# PSU_MGTAVCC_Buck.net
KiCad netlist of a schematic drawn in Altium Designer
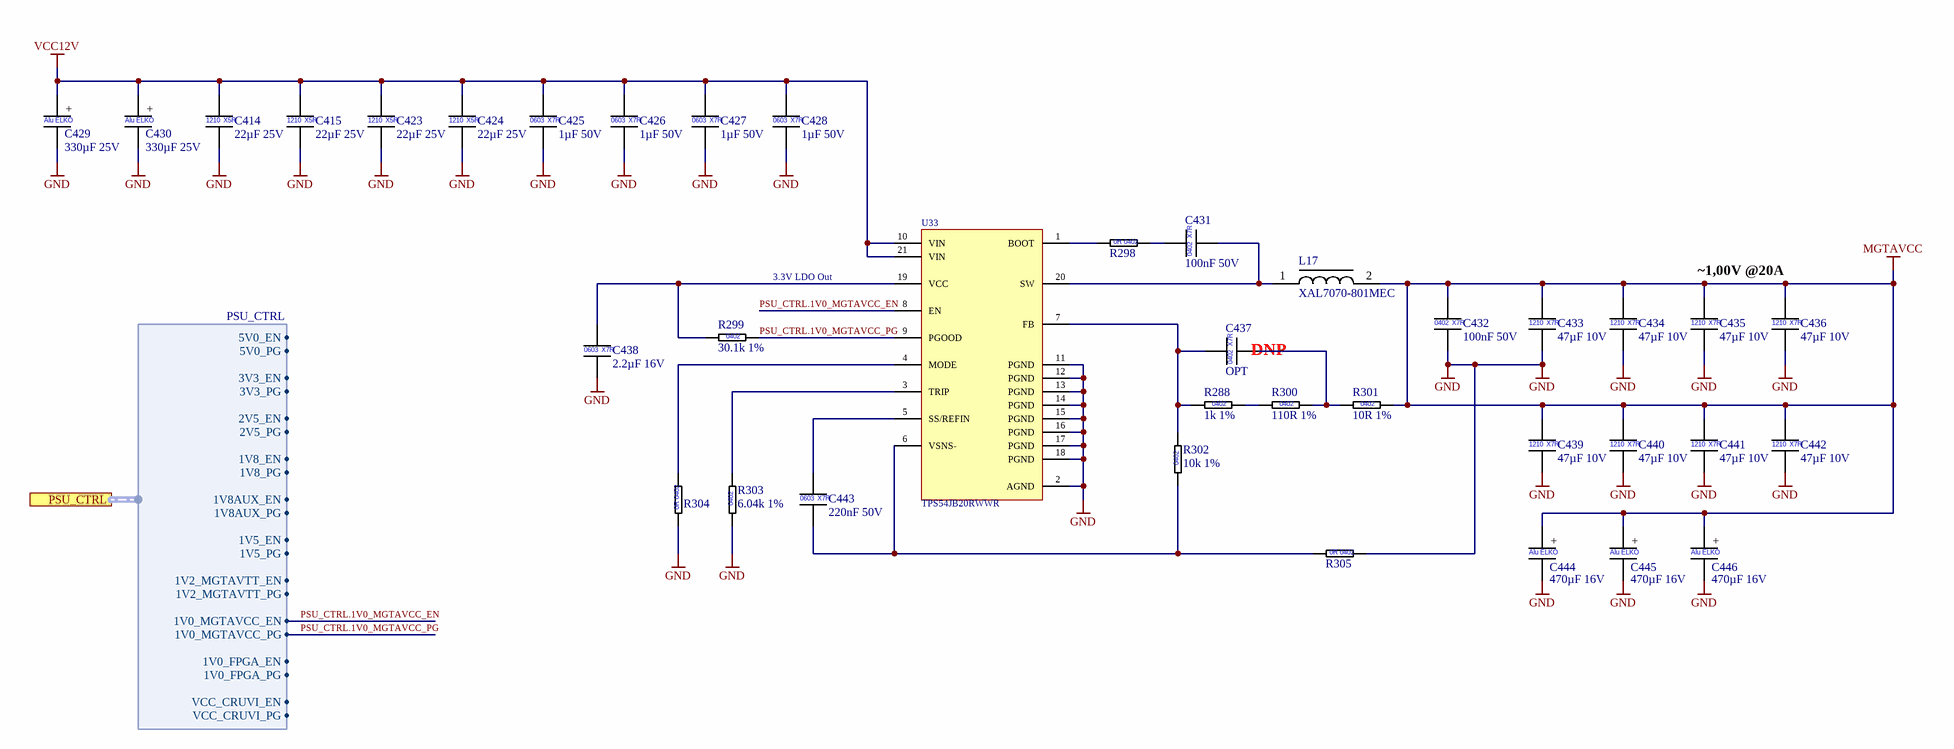
[diagram p0: PSU_MGTAVCC_Buck.SchDoc]

(export (version "E")
  (design (tool "Eeschema 10.0.6"))
  (components
    (comp (ref "C414")
      (value "22µF 25V")
      (footprint "Cap:CAP_1210")
      (description "Multilayer Ceramic Capacitors MLCC - SMD/SMT 1210 25VDC")
      (libsource (lib "Cap") (part "CAP_1210_22µF_25V"))
    )
    (comp (ref "C415")
      (value "22µF 25V")
      (footprint "Cap:CAP_1210")
      (description "Multilayer Ceramic Capacitors MLCC - SMD/SMT 1210 25VDC")
      (libsource (lib "Cap") (part "CAP_1210_22µF_25V"))
    )
    (comp (ref "C423")
      (value "22µF 25V")
      (footprint "Cap:CAP_1210")
      (description "Multilayer Ceramic Capacitors MLCC - SMD/SMT 1210 25VDC")
      (libsource (lib "Cap") (part "CAP_1210_22µF_25V"))
    )
    (comp (ref "C424")
      (value "22µF 25V")
      (footprint "Cap:CAP_1210")
      (description "Multilayer Ceramic Capacitors MLCC - SMD/SMT 1210 25VDC")
      (libsource (lib "Cap") (part "CAP_1210_22µF_25V"))
    )
    (comp (ref "C425")
      (value "1µF 50V")
      (footprint "CAP_0603")
      (description "Multilayer Ceramic Capacitors MLCC - SMD/SMT 50V 1uF X7R 0603 10%")
      (libsource (lib "Cap") (part "CAP_0603_1µF_50V_X7R_10%"))
    )
    (comp (ref "C426")
      (value "1µF 50V")
      (footprint "CAP_0603")
      (description "Multilayer Ceramic Capacitors MLCC - SMD/SMT 50V 1uF X7R 0603 10%")
      (libsource (lib "Cap") (part "CAP_0603_1µF_50V_X7R_10%"))
    )
    (comp (ref "C427")
      (value "1µF 50V")
      (footprint "CAP_0603")
      (description "Multilayer Ceramic Capacitors MLCC - SMD/SMT 50V 1uF X7R 0603 10%")
      (libsource (lib "Cap") (part "CAP_0603_1µF_50V_X7R_10%"))
    )
    (comp (ref "C428")
      (value "1µF 50V")
      (footprint "CAP_0603")
      (description "Multilayer Ceramic Capacitors MLCC - SMD/SMT 50V 1uF X7R 0603 10%")
      (libsource (lib "Cap") (part "CAP_0603_1µF_50V_X7R_10%"))
    )
    (comp (ref "C429")
      (value "330µF 25V")
      (footprint "Cap:WCAP-PTG5_D10H12.5")
      (description "Organische Polymer-Aluminiumkondensatoren 330uF 25 Volts 20% AEC-Q200")
      (libsource (lib "Cap") (part "CAP_D10L12.5_330µF_25V"))
    )
    (comp (ref "C430")
      (value "330µF 25V")
      (footprint "Cap:WCAP-PTG5_D10H12.5")
      (description "Organische Polymer-Aluminiumkondensatoren 330uF 25 Volts 20% AEC-Q200")
      (libsource (lib "Cap") (part "CAP_D10L12.5_330µF_25V"))
    )
    (comp (ref "C431")
      (value "100nF 50V")
      (footprint "Cap:CAP_0402")
      (description "Multilayer Ceramic Capacitors MLCC - SMD/SMT 0402 50VDC")
      (libsource (lib "Cap") (part "CAP_0402_100nF_50V"))
    )
    (comp (ref "C432")
      (value "100nF 50V")
      (footprint "Cap:CAP_0402")
      (description "Multilayer Ceramic Capacitors MLCC - SMD/SMT 0402 50VDC")
      (libsource (lib "") (part "CAP_0402_100nF_50V_1"))
    )
    (comp (ref "C433")
      (value "47µF 10V")
      (footprint "Cap:CAP_1210")
      (description "Multilayer Ceramic Capacitors MLCC - SMD/SMT 47 uF 10 VDC 10% 1210 X7R")
      (libsource (lib "Cap") (part "CAP_1210_47µF_10V_X7R_10%"))
    )
    (comp (ref "C434")
      (value "47µF 10V")
      (footprint "Cap:CAP_1210")
      (description "Multilayer Ceramic Capacitors MLCC - SMD/SMT 47 uF 10 VDC 10% 1210 X7R")
      (libsource (lib "Cap") (part "CAP_1210_47µF_10V_X7R_10%"))
    )
    (comp (ref "C435")
      (value "47µF 10V")
      (footprint "Cap:CAP_1210")
      (description "Multilayer Ceramic Capacitors MLCC - SMD/SMT 47 uF 10 VDC 10% 1210 X7R")
      (libsource (lib "Cap") (part "CAP_1210_47µF_10V_X7R_10%"))
    )
    (comp (ref "C436")
      (value "47µF 10V")
      (footprint "Cap:CAP_1210")
      (description "Multilayer Ceramic Capacitors MLCC - SMD/SMT 47 uF 10 VDC 10% 1210 X7R")
      (libsource (lib "Cap") (part "CAP_1210_47µF_10V_X7R_10%"))
    )
    (comp (ref "C437")
      (value "OPT")
      (footprint "Cap:CAP_0402")
      (description "Multilayer Ceramic Capacitors MLCC - SMD/SMT 0402 Optional Placeholder")
      (libsource (lib "Cap") (part "CAP_0402_OPT"))
    )
    (comp (ref "C438")
      (value "2.2µF 16V")
      (footprint "Cap:CAP_0603")
      (description "Multilayer Ceramic Capacitors MLCC - SMD/SMT 2.2 uF 16 VDC 10% 0603 X7R")
      (libsource (lib "Cap") (part "CAP_0603_2.2µF_16V_X7R_10%"))
    )
    (comp (ref "C439")
      (value "47µF 10V")
      (footprint "Cap:CAP_1210")
      (description "Multilayer Ceramic Capacitors MLCC - SMD/SMT 47 uF 10 VDC 10% 1210 X7R")
      (libsource (lib "Cap") (part "CAP_1210_47µF_10V_X7R_10%"))
    )
    (comp (ref "C440")
      (value "47µF 10V")
      (footprint "Cap:CAP_1210")
      (description "Multilayer Ceramic Capacitors MLCC - SMD/SMT 47 uF 10 VDC 10% 1210 X7R")
      (libsource (lib "Cap") (part "CAP_1210_47µF_10V_X7R_10%"))
    )
    (comp (ref "C441")
      (value "47µF 10V")
      (footprint "Cap:CAP_1210")
      (description "Multilayer Ceramic Capacitors MLCC - SMD/SMT 47 uF 10 VDC 10% 1210 X7R")
      (libsource (lib "Cap") (part "CAP_1210_47µF_10V_X7R_10%"))
    )
    (comp (ref "C442")
      (value "47µF 10V")
      (footprint "Cap:CAP_1210")
      (description "Multilayer Ceramic Capacitors MLCC - SMD/SMT 47 uF 10 VDC 10% 1210 X7R")
      (libsource (lib "Cap") (part "CAP_1210_47µF_10V_X7R_10%"))
    )
    (comp (ref "C443")
      (value "220nF 50V")
      (footprint "CAP_0603")
      (description "Multilayer Ceramic Capacitors MLCC - SMD/SMT 0.22 uF 50 VDC 10% 0603 X7R")
      (libsource (lib "Cap") (part "CAP_0603_220nF_50V_X7R_10%"))
    )
    (comp (ref "C444")
      (value "470µF 16V")
      (footprint "Cap:WCAP-PTG5_D8H13")
      (description "Organische Polymer-Aluminiumkondensatoren 470uF 16 Volts 20%")
      (libsource (lib "Cap") (part "CAP_D8L9_470µF_16V"))
    )
    (comp (ref "C445")
      (value "470µF 16V")
      (footprint "Cap:WCAP-PTG5_D8H13")
      (description "Organische Polymer-Aluminiumkondensatoren 470uF 16 Volts 20%")
      (libsource (lib "Cap") (part "CAP_D8L9_470µF_16V"))
    )
    (comp (ref "C446")
      (value "470µF 16V")
      (footprint "Cap:WCAP-PTG5_D8H13")
      (description "Organische Polymer-Aluminiumkondensatoren 470uF 16 Volts 20%")
      (libsource (lib "Cap") (part "CAP_D8L9_470µF_16V"))
    )
    (comp (ref "L17")
      (value "XAL7070-801MEC")
      (footprint "indc:COILCRAFT_XAL7070")
      (description "Power Inductors - SMD 800nH Shld 20% 25.8A 2.29mOhms AECQ200")
      (libsource (lib "Indc") (part "XAL7070-801MEC_Power Inductors SMD 800nH Shld 20% 25.8A 2.29mOhms AECQ200"))
    )
    (comp (ref "R288")
      (value "1k 1%")
      (footprint "res:RES_0402")
      (description "Thick Film Resistors - SMD 1kOhm 1%")
      (libsource (lib "Res") (part "RES_0402_1k_1%"))
    )
    (comp (ref "R298")
      (value "0R Jumper")
      (footprint "res:RES_0402")
      (description "Thick Film Resistors - SMD 0Ohm")
      (libsource (lib "Res") (part "RES_0402_0R Jumper"))
    )
    (comp (ref "R299")
      (value "30.1k 1%")
      (footprint "res:RES_0402")
      (description "Thick Film Resistors - SMD 30.1kOhm 1%")
      (libsource (lib "Res") (part "RES_0402_30.1k_1%"))
    )
    (comp (ref "R300")
      (value "110R 1%")
      (footprint "res:RES_0402")
      (description "Thick Film Resistors - SMD 110Ohm 1%")
      (libsource (lib "Res") (part "RES_0402_110R_1%"))
    )
    (comp (ref "R301")
      (value "10R 1%")
      (footprint "res:RES_0402")
      (description "Thick Film Resistors - SMD 10Ohm 1%")
      (libsource (lib "Res") (part "RES_0402_10R_1%"))
    )
    (comp (ref "R302")
      (value "10k 1%")
      (footprint "Res:RES_0402")
      (description "Thick Film Resistors - SMD 10kOhm 1%")
      (libsource (lib "Res") (part "RES_0402_10k_1%"))
    )
    (comp (ref "R303")
      (value "6.04k 1%")
      (footprint "Res:RES_0402")
      (description "Thick Film Resistors - SMD 6.04kOhm 1%")
      (libsource (lib "Res") (part "RES_0402_6.04k_1%"))
    )
    (comp (ref "R304")
      (value "0R Jumper")
      (footprint "res:RES_0402")
      (description "Thick Film Resistors - SMD 0Ohm")
      (libsource (lib "Res") (part "RES_0402_0R Jumper"))
    )
    (comp (ref "R305")
      (value "0R Jumper")
      (footprint "res:RES_0402")
      (description "Thick Film Resistors - SMD 0Ohm")
      (libsource (lib "Res") (part "RES_0402_0R Jumper"))
    )
    (comp (ref "U33")
      (value "TPS54JB20RWWR")
      (footprint "power:VQFN-HR21_RWW0021A")
      (description "Switching Voltage Regulators 2.7-V to 16-V input 20-A synchronous Buck")
      (libsource (lib "Power") (part "TPS54JB20RWWR_Switching Voltage Regulators 2.7-V to 16-V input 20-A synchronous Buck"))
    )
  )
  (nets
    (net (code "2") (name "/PSU_CTRL.1V0_MGTAVCC_EN") (class "Default")
      (node (ref "U33") (pin "8") (pinfunction "EN_8") (pintype "passive"))
    )
    (net (code "3") (name "/PSU_CTRL.1V0_MGTAVCC_PG") (class "Default")
      (node (ref "R299") (pin "2") (pinfunction "2_2") (pintype "passive"))
      (node (ref "U33") (pin "9") (pinfunction "PGOOD_9") (pintype "passive"))
    )
    (net (code "5") (name "GND") (class "Default")
      (node (ref "C414") (pin "2") (pinfunction "2_2") (pintype "passive"))
      (node (ref "C415") (pin "2") (pinfunction "2_2") (pintype "passive"))
      (node (ref "C423") (pin "2") (pinfunction "2_2") (pintype "passive"))
      (node (ref "C424") (pin "2") (pinfunction "2_2") (pintype "passive"))
      (node (ref "C425") (pin "2") (pinfunction "2_2") (pintype "passive"))
      (node (ref "C426") (pin "2") (pinfunction "2_2") (pintype "passive"))
      (node (ref "C427") (pin "2") (pinfunction "2_2") (pintype "passive"))
      (node (ref "C428") (pin "2") (pinfunction "2_2") (pintype "passive"))
      (node (ref "C429") (pin "2") (pinfunction "2_2") (pintype "passive"))
      (node (ref "C430") (pin "2") (pinfunction "2_2") (pintype "passive"))
      (node (ref "C432") (pin "2") (pinfunction "2_2") (pintype "passive"))
      (node (ref "C433") (pin "2") (pinfunction "2_2") (pintype "passive"))
      (node (ref "C434") (pin "2") (pinfunction "2_2") (pintype "passive"))
      (node (ref "C435") (pin "2") (pinfunction "2_2") (pintype "passive"))
      (node (ref "C436") (pin "2") (pinfunction "2_2") (pintype "passive"))
      (node (ref "C438") (pin "2") (pinfunction "2_2") (pintype "passive"))
      (node (ref "C439") (pin "2") (pinfunction "2_2") (pintype "passive"))
      (node (ref "C440") (pin "2") (pinfunction "2_2") (pintype "passive"))
      (node (ref "C441") (pin "2") (pinfunction "2_2") (pintype "passive"))
      (node (ref "C442") (pin "2") (pinfunction "2_2") (pintype "passive"))
      (node (ref "C444") (pin "2") (pinfunction "2_2") (pintype "passive"))
      (node (ref "C445") (pin "2") (pinfunction "2_2") (pintype "passive"))
      (node (ref "C446") (pin "2") (pinfunction "2_2") (pintype "passive"))
      (node (ref "R303") (pin "1") (pinfunction "1_1") (pintype "passive"))
      (node (ref "R304") (pin "1") (pinfunction "1_1") (pintype "passive"))
      (node (ref "R305") (pin "2") (pinfunction "2_2") (pintype "passive"))
      (node (ref "U33") (pin "11") (pinfunction "PGND_11") (pintype "passive"))
      (node (ref "U33") (pin "12") (pinfunction "PGND_12") (pintype "passive"))
      (node (ref "U33") (pin "13") (pinfunction "PGND_13") (pintype "passive"))
      (node (ref "U33") (pin "14") (pinfunction "PGND_14") (pintype "passive"))
      (node (ref "U33") (pin "15") (pinfunction "PGND_15") (pintype "passive"))
      (node (ref "U33") (pin "16") (pinfunction "PGND_16") (pintype "passive"))
      (node (ref "U33") (pin "17") (pinfunction "PGND_17") (pintype "passive"))
      (node (ref "U33") (pin "18") (pinfunction "PGND_18") (pintype "passive"))
      (node (ref "U33") (pin "2") (pinfunction "AGND_2") (pintype "passive"))
    )
    (net (code "6") (name "MGTAVCC") (class "Default")
      (node (ref "C432") (pin "1") (pinfunction "1_1") (pintype "passive"))
      (node (ref "C433") (pin "1") (pinfunction "1_1") (pintype "passive"))
      (node (ref "C434") (pin "1") (pinfunction "1_1") (pintype "passive"))
      (node (ref "C435") (pin "1") (pinfunction "1_1") (pintype "passive"))
      (node (ref "C436") (pin "1") (pinfunction "1_1") (pintype "passive"))
      (node (ref "C439") (pin "1") (pinfunction "1_1") (pintype "passive"))
      (node (ref "C440") (pin "1") (pinfunction "1_1") (pintype "passive"))
      (node (ref "C441") (pin "1") (pinfunction "1_1") (pintype "passive"))
      (node (ref "C442") (pin "1") (pinfunction "1_1") (pintype "passive"))
      (node (ref "C444") (pin "1") (pinfunction "1_1") (pintype "passive"))
      (node (ref "C445") (pin "1") (pinfunction "1_1") (pintype "passive"))
      (node (ref "C446") (pin "1") (pinfunction "1_1") (pintype "passive"))
      (node (ref "L17") (pin "2") (pinfunction "2_2") (pintype "passive"))
      (node (ref "R301") (pin "2") (pinfunction "2_2") (pintype "passive"))
    )
    (net (code "7") (name "Net-(C431-Pad1)") (class "Default")
      (node (ref "C431") (pin "1") (pinfunction "1_1") (pintype "passive"))
      (node (ref "R298") (pin "2") (pinfunction "2_2") (pintype "passive"))
    )
    (net (code "8") (name "Net-(C437-Pad2)") (class "Default")
      (node (ref "C437") (pin "2") (pinfunction "2_2") (pintype "passive"))
      (node (ref "R300") (pin "2") (pinfunction "2_2") (pintype "passive"))
      (node (ref "R301") (pin "1") (pinfunction "1_1") (pintype "passive"))
    )
    (net (code "9") (name "Net-(R288-Pad2)") (class "Default")
      (node (ref "R288") (pin "2") (pinfunction "2_2") (pintype "passive"))
      (node (ref "R300") (pin "1") (pinfunction "1_1") (pintype "passive"))
    )
    (net (code "10") (name "Net-(U33-BOOT)") (class "Default")
      (node (ref "R298") (pin "1") (pinfunction "1_1") (pintype "passive"))
      (node (ref "U33") (pin "1") (pinfunction "BOOT_1") (pintype "passive"))
    )
    (net (code "11") (name "Net-(U33-FB)") (class "Default")
      (node (ref "C437") (pin "1") (pinfunction "1_1") (pintype "passive"))
      (node (ref "R288") (pin "1") (pinfunction "1_1") (pintype "passive"))
      (node (ref "R302") (pin "2") (pinfunction "2_2") (pintype "passive"))
      (node (ref "U33") (pin "7") (pinfunction "FB_7") (pintype "passive"))
    )
    (net (code "12") (name "Net-(U33-MODE)") (class "Default")
      (node (ref "R304") (pin "2") (pinfunction "2_2") (pintype "passive"))
      (node (ref "U33") (pin "4") (pinfunction "MODE_4") (pintype "passive"))
    )
    (net (code "13") (name "Net-(U33-SS{slash}REFIN)") (class "Default")
      (node (ref "C443") (pin "1") (pinfunction "1_1") (pintype "passive"))
      (node (ref "U33") (pin "5") (pinfunction "SS/REFIN_5") (pintype "passive"))
    )
    (net (code "14") (name "Net-(U33-SW)") (class "Default")
      (node (ref "C431") (pin "2") (pinfunction "2_2") (pintype "passive"))
      (node (ref "L17") (pin "1") (pinfunction "1_1") (pintype "passive"))
      (node (ref "U33") (pin "20") (pinfunction "SW_20") (pintype "passive"))
    )
    (net (code "15") (name "Net-(U33-TRIP)") (class "Default")
      (node (ref "R303") (pin "2") (pinfunction "2_2") (pintype "passive"))
      (node (ref "U33") (pin "3") (pinfunction "TRIP_3") (pintype "passive"))
    )
    (net (code "16") (name "Net-(U33-VCC)") (class "Default")
      (node (ref "C438") (pin "1") (pinfunction "1_1") (pintype "passive"))
      (node (ref "R299") (pin "1") (pinfunction "1_1") (pintype "passive"))
      (node (ref "U33") (pin "19") (pinfunction "VCC_19") (pintype "passive"))
    )
    (net (code "17") (name "Net-(U33-VSNS-)") (class "Default")
      (node (ref "C443") (pin "2") (pinfunction "2_2") (pintype "passive"))
      (node (ref "R302") (pin "1") (pinfunction "1_1") (pintype "passive"))
      (node (ref "R305") (pin "1") (pinfunction "1_1") (pintype "passive"))
      (node (ref "U33") (pin "6") (pinfunction "VSNS-_6") (pintype "passive"))
    )
    (net (code "18") (name "VCC12V") (class "Default")
      (node (ref "C414") (pin "1") (pinfunction "1_1") (pintype "passive"))
      (node (ref "C415") (pin "1") (pinfunction "1_1") (pintype "passive"))
      (node (ref "C423") (pin "1") (pinfunction "1_1") (pintype "passive"))
      (node (ref "C424") (pin "1") (pinfunction "1_1") (pintype "passive"))
      (node (ref "C425") (pin "1") (pinfunction "1_1") (pintype "passive"))
      (node (ref "C426") (pin "1") (pinfunction "1_1") (pintype "passive"))
      (node (ref "C427") (pin "1") (pinfunction "1_1") (pintype "passive"))
      (node (ref "C428") (pin "1") (pinfunction "1_1") (pintype "passive"))
      (node (ref "C429") (pin "1") (pinfunction "1_1") (pintype "passive"))
      (node (ref "C430") (pin "1") (pinfunction "1_1") (pintype "passive"))
      (node (ref "U33") (pin "10") (pinfunction "VIN_10") (pintype "passive"))
      (node (ref "U33") (pin "21") (pinfunction "VIN_21") (pintype "passive"))
    )
  )
)
